# M452x.net
KiCad netlist of a schematic drawn in EAGLE
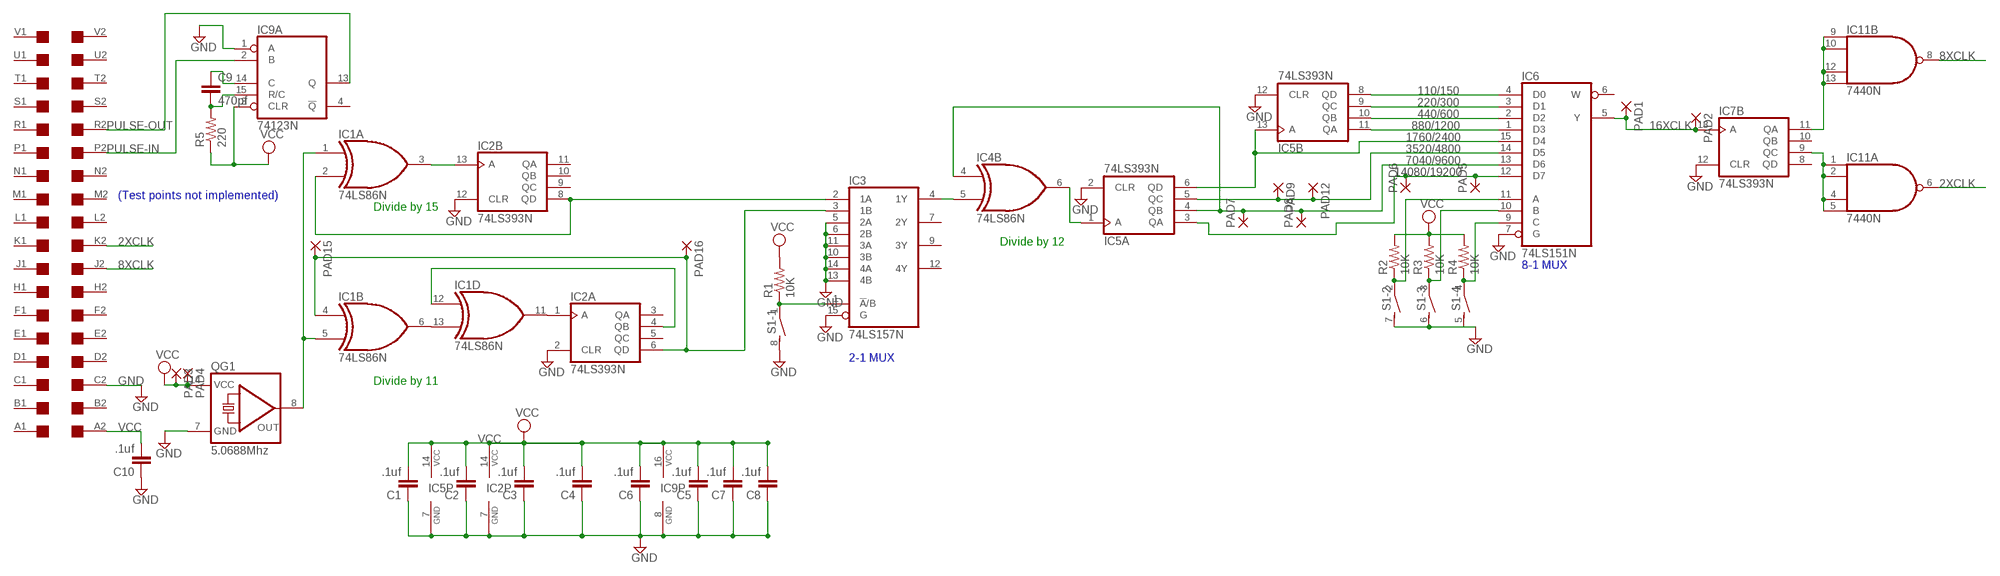
[diagram p0: schematic, sheet 1]

(export (version "E")
  (design (tool "Eeschema 10.0.6"))
  (components
    (comp (ref "C1")
      (value ".1uf")
      (footprint "eagle-import:C050-025X075")
      (libsource (lib "eagle-import") (part "C-EU050-025X075"))
    )
    (comp (ref "C2")
      (value ".1uf")
      (footprint "eagle-import:C050-025X075")
      (libsource (lib "eagle-import") (part "C-EU050-025X075"))
    )
    (comp (ref "C3")
      (value ".1uf")
      (footprint "eagle-import:C050-025X075")
      (libsource (lib "eagle-import") (part "C-EU050-025X075"))
    )
    (comp (ref "C4")
      (value ".1uf")
      (footprint "eagle-import:C050-025X075")
      (libsource (lib "eagle-import") (part "C-EU050-025X075"))
    )
    (comp (ref "C5")
      (value ".1uf")
      (footprint "eagle-import:C050-025X075")
      (libsource (lib "eagle-import") (part "C-EU050-025X075"))
    )
    (comp (ref "C6")
      (value ".1uf")
      (footprint "eagle-import:C050-025X075")
      (libsource (lib "eagle-import") (part "C-EU050-025X075"))
    )
    (comp (ref "C7")
      (value ".1uf")
      (footprint "eagle-import:C050-025X075")
      (libsource (lib "eagle-import") (part "C-EU050-025X075"))
    )
    (comp (ref "C8")
      (value ".1uf")
      (footprint "eagle-import:C050-025X075")
      (libsource (lib "eagle-import") (part "C-EU050-025X075"))
    )
    (comp (ref "C9")
      (value "470pf")
      (footprint "eagle-import:C050-025X075")
      (libsource (lib "eagle-import") (part "C-EU050-025X075"))
    )
    (comp (ref "C10")
      (value ".1uf")
      (footprint "eagle-import:C050-025X075")
      (libsource (lib "eagle-import") (part "C-EU050-025X075"))
    )
    (comp (ref "IC1")
      (value "74LS86N")
      (footprint "eagle-import:DIL14")
      (libsource (lib "eagle-import") (part "7486NLS"))
    )
    (comp (ref "IC2")
      (value "74LS393N")
      (footprint "eagle-import:DIL14")
      (libsource (lib "eagle-import") (part "74393NLS"))
    )
    (comp (ref "IC3")
      (value "74LS157N")
      (footprint "eagle-import:DIL16")
      (libsource (lib "eagle-import") (part "74157NLS"))
    )
    (comp (ref "IC4")
      (value "74LS86N")
      (footprint "eagle-import:DIL14")
      (libsource (lib "eagle-import") (part "7486NLS"))
    )
    (comp (ref "IC5")
      (value "74LS393N")
      (footprint "eagle-import:DIL14")
      (libsource (lib "eagle-import") (part "74393NLS"))
    )
    (comp (ref "IC6")
      (value "74LS151N")
      (footprint "eagle-import:DIL16")
      (libsource (lib "eagle-import") (part "74151N"))
    )
    (comp (ref "IC7")
      (value "74LS393N")
      (footprint "eagle-import:DIL14")
      (libsource (lib "eagle-import") (part "74393NLS"))
    )
    (comp (ref "IC9")
      (value "74123N")
      (footprint "eagle-import:DIL16")
      (libsource (lib "eagle-import") (part "74123N"))
    )
    (comp (ref "IC11")
      (value "7440N")
      (footprint "eagle-import:DIL14")
      (libsource (lib "eagle-import") (part "7420NS"))
    )
    (comp (ref "PAD1")
      (value "1,6/0,8")
      (footprint "eagle-import:1,6_0,8")
      (libsource (lib "eagle-import") (part "1,6/0,8"))
    )
    (comp (ref "PAD2")
      (value "1,6/0,8")
      (footprint "eagle-import:1,6_0,8")
      (libsource (lib "eagle-import") (part "1,6/0,8"))
    )
    (comp (ref "PAD3")
      (value "1,6/0,8")
      (footprint "eagle-import:1,6_0,8")
      (libsource (lib "eagle-import") (part "1,6/0,8"))
    )
    (comp (ref "PAD4")
      (value "1,6/0,8")
      (footprint "eagle-import:1,6_0,8")
      (libsource (lib "eagle-import") (part "1,6/0,8"))
    )
    (comp (ref "PAD5")
      (value "1,6/0,8")
      (footprint "eagle-import:1,6_0,8")
      (libsource (lib "eagle-import") (part "1,6/0,8"))
    )
    (comp (ref "PAD6")
      (value "1,6/0,8")
      (footprint "eagle-import:1,6_0,8")
      (libsource (lib "eagle-import") (part "1,6/0,8"))
    )
    (comp (ref "PAD7")
      (value "1,6/0,8")
      (footprint "eagle-import:1,6_0,8")
      (libsource (lib "eagle-import") (part "1,6/0,8"))
    )
    (comp (ref "PAD8")
      (value "1,6/0,8")
      (footprint "eagle-import:1,6_0,8")
      (libsource (lib "eagle-import") (part "1,6/0,8"))
    )
    (comp (ref "PAD9")
      (value "1,6/0,8")
      (footprint "eagle-import:1,6_0,8")
      (libsource (lib "eagle-import") (part "1,6/0,8"))
    )
    (comp (ref "PAD12")
      (value "1,6/0,8")
      (footprint "eagle-import:1,6_0,8")
      (libsource (lib "eagle-import") (part "1,6/0,8"))
    )
    (comp (ref "PAD15")
      (value "1,6/0,8")
      (footprint "eagle-import:1,6_0,8")
      (libsource (lib "eagle-import") (part "1,6/0,8"))
    )
    (comp (ref "PAD16")
      (value "1,6/0,8")
      (footprint "eagle-import:1,6_0,8")
      (libsource (lib "eagle-import") (part "1,6/0,8"))
    )
    (comp (ref "QG1")
      (value "5.0688Mhz")
      (footprint "eagle-import:DIL14S")
      (libsource (lib "eagle-import") (part "QG5860"))
    )
    (comp (ref "R1")
      (value "10K")
      (footprint "eagle-import:0204_7")
      (libsource (lib "eagle-import") (part "R-US_0204/7"))
    )
    (comp (ref "R2")
      (value "10K")
      (footprint "eagle-import:0204_7")
      (libsource (lib "eagle-import") (part "R-US_0204/7"))
    )
    (comp (ref "R3")
      (value "10K")
      (footprint "eagle-import:0204_7")
      (libsource (lib "eagle-import") (part "R-US_0204/7"))
    )
    (comp (ref "R4")
      (value "10K")
      (footprint "eagle-import:0204_7")
      (libsource (lib "eagle-import") (part "R-US_0204/7"))
    )
    (comp (ref "R5")
      (value "220")
      (footprint "eagle-import:0204_7")
      (libsource (lib "eagle-import") (part "R-US_0204/7"))
    )
    (comp (ref "S1")
      (value "DIP04S")
      (footprint "eagle-import:DIP04S")
      (libsource (lib "eagle-import") (part "DIP04S"))
    )
    (comp (ref "U$1")
      (value "DEC-FLIPCHIP")
      (footprint "eagle-import:DEC-FLIPCHIP")
      (libsource (lib "eagle-import") (part "DEC-FLIPCHIP"))
    )
  )
  (nets
    (net (code "1") (name "/2XCLK") (class "Default")
      (node (ref "IC11") (pin "6") (pinfunction "O_6") (pintype "output"))
      (node (ref "U$1") (pin "K2") (pinfunction "K2_K2") (pintype "passive"))
    )
    (net (code "2") (name "/8XCLK") (class "Default")
      (node (ref "IC11") (pin "8") (pinfunction "O_8") (pintype "output"))
      (node (ref "U$1") (pin "J2") (pinfunction "J2_J2") (pintype "passive"))
    )
    (net (code "3") (name "/16XCLK") (class "Default")
      (node (ref "IC6") (pin "5") (pinfunction "Y_5") (pintype "output"))
      (node (ref "IC7") (pin "13") (pinfunction "A_13") (pintype "input"))
      (node (ref "PAD1") (pin "1") (pinfunction "P_1") (pintype "passive"))
      (node (ref "PAD2") (pin "1") (pinfunction "P_1") (pintype "passive"))
    )
    (net (code "4") (name "/110{slash}150") (class "Default")
      (node (ref "IC5") (pin "8") (pinfunction "QD_8") (pintype "output"))
      (node (ref "IC6") (pin "4") (pinfunction "D0_4") (pintype "input"))
    )
    (net (code "5") (name "/220{slash}300") (class "Default")
      (node (ref "IC5") (pin "9") (pinfunction "QC_9") (pintype "output"))
      (node (ref "IC6") (pin "3") (pinfunction "D1_3") (pintype "input"))
    )
    (net (code "6") (name "/440{slash}600") (class "Default")
      (node (ref "IC5") (pin "10") (pinfunction "QB_10") (pintype "output"))
      (node (ref "IC6") (pin "2") (pinfunction "D2_2") (pintype "input"))
    )
    (net (code "7") (name "/880{slash}1200") (class "Default")
      (node (ref "IC5") (pin "11") (pinfunction "QA_11") (pintype "output"))
      (node (ref "IC6") (pin "1") (pinfunction "D3_1") (pintype "input"))
    )
    (net (code "8") (name "/1760{slash}2400") (class "Default")
      (node (ref "IC5") (pin "13") (pinfunction "A_13") (pintype "input"))
      (node (ref "IC5") (pin "6") (pinfunction "QD_6") (pintype "output"))
      (node (ref "IC6") (pin "15") (pinfunction "D4_15") (pintype "input"))
    )
    (net (code "9") (name "/3520{slash}4800") (class "Default")
      (node (ref "IC5") (pin "5") (pinfunction "QC_5") (pintype "output"))
      (node (ref "IC6") (pin "14") (pinfunction "D5_14") (pintype "input"))
      (node (ref "PAD12") (pin "1") (pinfunction "P_1") (pintype "passive"))
      (node (ref "PAD9") (pin "1") (pinfunction "P_1") (pintype "passive"))
    )
    (net (code "10") (name "/7040{slash}9600") (class "Default")
      (node (ref "IC4") (pin "4") (pinfunction "I0_4") (pintype "input"))
      (node (ref "IC5") (pin "4") (pinfunction "QB_4") (pintype "output"))
      (node (ref "IC6") (pin "13") (pinfunction "D6_13") (pintype "input"))
      (node (ref "PAD7") (pin "1") (pinfunction "P_1") (pintype "passive"))
      (node (ref "PAD8") (pin "1") (pinfunction "P_1") (pintype "passive"))
    )
    (net (code "11") (name "/14080{slash}19200") (class "Default")
      (node (ref "IC5") (pin "3") (pinfunction "QA_3") (pintype "output"))
      (node (ref "IC6") (pin "12") (pinfunction "D7_12") (pintype "input"))
      (node (ref "PAD5") (pin "1") (pinfunction "P_1") (pintype "passive"))
      (node (ref "PAD6") (pin "1") (pinfunction "P_1") (pintype "passive"))
    )
    (net (code "12") (name "/PULSE-IN") (class "Default")
      (node (ref "IC9") (pin "2") (pinfunction "B_2") (pintype "input"))
      (node (ref "U$1") (pin "P2") (pinfunction "P2_P2") (pintype "passive"))
    )
    (net (code "13") (name "/PULSE-OUT") (class "Default")
      (node (ref "IC9") (pin "13") (pinfunction "Q_13") (pintype "output"))
      (node (ref "U$1") (pin "R2") (pinfunction "R2_R2") (pintype "passive"))
    )
    (net (code "14") (name "GND") (class "Default")
      (node (ref "C1") (pin "1") (pinfunction "1_1") (pintype "passive"))
      (node (ref "C10") (pin "1") (pinfunction "1_1") (pintype "passive"))
      (node (ref "C2") (pin "1") (pinfunction "1_1") (pintype "passive"))
      (node (ref "C3") (pin "1") (pinfunction "1_1") (pintype "passive"))
      (node (ref "C4") (pin "1") (pinfunction "1_1") (pintype "passive"))
      (node (ref "C5") (pin "1") (pinfunction "1_1") (pintype "passive"))
      (node (ref "C6") (pin "1") (pinfunction "1_1") (pintype "passive"))
      (node (ref "C7") (pin "1") (pinfunction "1_1") (pintype "passive"))
      (node (ref "C8") (pin "1") (pinfunction "1_1") (pintype "passive"))
      (node (ref "IC2") (pin "12") (pinfunction "CLR_12") (pintype "input"))
      (node (ref "IC2") (pin "2") (pinfunction "CLR_2") (pintype "input"))
      (node (ref "IC2") (pin "7") (pinfunction "GND_7") (pintype "power_in"))
      (node (ref "IC3") (pin "10") (pinfunction "3B_10") (pintype "input"))
      (node (ref "IC3") (pin "11") (pinfunction "3A_11") (pintype "input"))
      (node (ref "IC3") (pin "13") (pinfunction "4B_13") (pintype "input"))
      (node (ref "IC3") (pin "14") (pinfunction "4A_14") (pintype "input"))
      (node (ref "IC3") (pin "15") (pinfunction "G_15") (pintype "input"))
      (node (ref "IC3") (pin "5") (pinfunction "2A_5") (pintype "input"))
      (node (ref "IC3") (pin "6") (pinfunction "2B_6") (pintype "input"))
      (node (ref "IC5") (pin "12") (pinfunction "CLR_12") (pintype "input"))
      (node (ref "IC5") (pin "2") (pinfunction "CLR_2") (pintype "input"))
      (node (ref "IC5") (pin "7") (pinfunction "GND_7") (pintype "power_in"))
      (node (ref "IC6") (pin "7") (pinfunction "G_7") (pintype "input"))
      (node (ref "IC7") (pin "12") (pinfunction "CLR_12") (pintype "input"))
      (node (ref "IC9") (pin "1") (pinfunction "A_1") (pintype "input"))
      (node (ref "IC9") (pin "8") (pinfunction "GND_8") (pintype "power_in"))
      (node (ref "QG1") (pin "7") (pinfunction "GND_7") (pintype "power_in"))
      (node (ref "S1") (pin "5") (pinfunction "2_5") (pintype "passive"))
      (node (ref "S1") (pin "6") (pinfunction "2_6") (pintype "passive"))
      (node (ref "S1") (pin "7") (pinfunction "2_7") (pintype "passive"))
      (node (ref "S1") (pin "8") (pinfunction "2_8") (pintype "passive"))
      (node (ref "U$1") (pin "C2") (pinfunction "C2_C2") (pintype "passive"))
    )
    (net (code "15") (name "Net-(IC1A-I0)") (class "Default")
      (node (ref "IC1") (pin "1") (pinfunction "I0_1") (pintype "input"))
      (node (ref "IC1") (pin "5") (pinfunction "I1_5") (pintype "input"))
      (node (ref "QG1") (pin "8") (pinfunction "OUT_8") (pintype "output"))
    )
    (net (code "16") (name "Net-(IC1A-I1)") (class "Default")
      (node (ref "IC1") (pin "2") (pinfunction "I1_2") (pintype "input"))
      (node (ref "IC2") (pin "8") (pinfunction "QD_8") (pintype "output"))
      (node (ref "IC3") (pin "2") (pinfunction "1A_2") (pintype "input"))
    )
    (net (code "17") (name "Net-(IC1A-O)") (class "Default")
      (node (ref "IC1") (pin "3") (pinfunction "O_3") (pintype "output"))
      (node (ref "IC2") (pin "13") (pinfunction "A_13") (pintype "input"))
    )
    (net (code "18") (name "Net-(IC1B-I0)") (class "Default")
      (node (ref "IC1") (pin "4") (pinfunction "I0_4") (pintype "input"))
      (node (ref "IC2") (pin "6") (pinfunction "QD_6") (pintype "output"))
      (node (ref "IC3") (pin "3") (pinfunction "1B_3") (pintype "input"))
      (node (ref "PAD15") (pin "1") (pinfunction "P_1") (pintype "passive"))
      (node (ref "PAD16") (pin "1") (pinfunction "P_1") (pintype "passive"))
    )
    (net (code "19") (name "Net-(IC1B-O)") (class "Default")
      (node (ref "IC1") (pin "13") (pinfunction "I1_13") (pintype "input"))
      (node (ref "IC1") (pin "6") (pinfunction "O_6") (pintype "output"))
    )
    (net (code "20") (name "Net-(IC1D-I0)") (class "Default")
      (node (ref "IC1") (pin "12") (pinfunction "I0_12") (pintype "input"))
      (node (ref "IC2") (pin "4") (pinfunction "QB_4") (pintype "output"))
    )
    (net (code "21") (name "Net-(IC1D-O)") (class "Default")
      (node (ref "IC1") (pin "11") (pinfunction "O_11") (pintype "output"))
      (node (ref "IC2") (pin "1") (pinfunction "A_1") (pintype "input"))
    )
    (net (code "22") (name "Net-(IC3A-1Y)") (class "Default")
      (node (ref "IC3") (pin "4") (pinfunction "1Y_4") (pintype "output"))
      (node (ref "IC4") (pin "5") (pinfunction "I1_5") (pintype "input"))
    )
    (net (code "23") (name "Net-(IC3A-~{A}{slash}B)") (class "Default")
      (node (ref "IC3") (pin "1") (pinfunction "~{A}/B_1") (pintype "input"))
      (node (ref "R1") (pin "1") (pinfunction "1_1") (pintype "passive"))
      (node (ref "S1") (pin "1") (pinfunction "1_1") (pintype "passive"))
    )
    (net (code "24") (name "Net-(IC4B-O)") (class "Default")
      (node (ref "IC4") (pin "6") (pinfunction "O_6") (pintype "output"))
      (node (ref "IC5") (pin "1") (pinfunction "A_1") (pintype "input"))
    )
    (net (code "25") (name "Net-(IC6A-A)") (class "Default")
      (node (ref "IC6") (pin "11") (pinfunction "A_11") (pintype "input"))
      (node (ref "R2") (pin "1") (pinfunction "1_1") (pintype "passive"))
      (node (ref "S1") (pin "2") (pinfunction "1_2") (pintype "passive"))
    )
    (net (code "26") (name "Net-(IC6A-B)") (class "Default")
      (node (ref "IC6") (pin "10") (pinfunction "B_10") (pintype "input"))
      (node (ref "R3") (pin "1") (pinfunction "1_1") (pintype "passive"))
      (node (ref "S1") (pin "3") (pinfunction "1_3") (pintype "passive"))
    )
    (net (code "27") (name "Net-(IC6A-C)") (class "Default")
      (node (ref "IC6") (pin "9") (pinfunction "C_9") (pintype "input"))
      (node (ref "R4") (pin "1") (pinfunction "1_1") (pintype "passive"))
      (node (ref "S1") (pin "4") (pinfunction "1_4") (pintype "passive"))
    )
    (net (code "28") (name "Net-(IC9A-C)") (class "Default")
      (node (ref "C9") (pin "1") (pinfunction "1_1") (pintype "passive"))
      (node (ref "IC9") (pin "14") (pinfunction "C_14") (pintype "input"))
    )
    (net (code "29") (name "Net-(IC9A-R{slash}C)") (class "Default")
      (node (ref "C9") (pin "2") (pinfunction "2_2") (pintype "passive"))
      (node (ref "IC9") (pin "15") (pinfunction "R/C_15") (pintype "input"))
      (node (ref "R5") (pin "2") (pinfunction "2_2") (pintype "passive"))
    )
    (net (code "30") (name "Net-(IC11A-I0)") (class "Default")
      (node (ref "IC11") (pin "1") (pinfunction "I0_1") (pintype "input"))
      (node (ref "IC11") (pin "2") (pinfunction "I1_2") (pintype "input"))
      (node (ref "IC11") (pin "4") (pinfunction "I2_4") (pintype "input"))
      (node (ref "IC11") (pin "5") (pinfunction "I3_5") (pintype "input"))
      (node (ref "IC7") (pin "9") (pinfunction "QC_9") (pintype "output"))
    )
    (net (code "31") (name "Net-(IC11B-I0)") (class "Default")
      (node (ref "IC11") (pin "10") (pinfunction "I1_10") (pintype "input"))
      (node (ref "IC11") (pin "12") (pinfunction "I2_12") (pintype "input"))
      (node (ref "IC11") (pin "13") (pinfunction "I3_13") (pintype "input"))
      (node (ref "IC11") (pin "9") (pinfunction "I0_9") (pintype "input"))
      (node (ref "IC7") (pin "11") (pinfunction "QA_11") (pintype "output"))
    )
    (net (code "32") (name "VCC") (class "Default")
      (node (ref "C1") (pin "2") (pinfunction "2_2") (pintype "passive"))
      (node (ref "C10") (pin "2") (pinfunction "2_2") (pintype "passive"))
      (node (ref "C2") (pin "2") (pinfunction "2_2") (pintype "passive"))
      (node (ref "C3") (pin "2") (pinfunction "2_2") (pintype "passive"))
      (node (ref "C4") (pin "2") (pinfunction "2_2") (pintype "passive"))
      (node (ref "C5") (pin "2") (pinfunction "2_2") (pintype "passive"))
      (node (ref "C6") (pin "2") (pinfunction "2_2") (pintype "passive"))
      (node (ref "C7") (pin "2") (pinfunction "2_2") (pintype "passive"))
      (node (ref "C8") (pin "2") (pinfunction "2_2") (pintype "passive"))
      (node (ref "IC2") (pin "14") (pinfunction "VCC_14") (pintype "power_in"))
      (node (ref "IC5") (pin "14") (pinfunction "VCC_14") (pintype "power_in"))
      (node (ref "IC9") (pin "16") (pinfunction "VCC_16") (pintype "power_in"))
      (node (ref "IC9") (pin "3") (pinfunction "CLR_3") (pintype "input"))
      (node (ref "PAD3") (pin "1") (pinfunction "P_1") (pintype "passive"))
      (node (ref "PAD4") (pin "1") (pinfunction "P_1") (pintype "passive"))
      (node (ref "QG1") (pin "14") (pinfunction "VCC_14") (pintype "power_in"))
      (node (ref "R1") (pin "2") (pinfunction "2_2") (pintype "passive"))
      (node (ref "R2") (pin "2") (pinfunction "2_2") (pintype "passive"))
      (node (ref "R3") (pin "2") (pinfunction "2_2") (pintype "passive"))
      (node (ref "R4") (pin "2") (pinfunction "2_2") (pintype "passive"))
      (node (ref "R5") (pin "1") (pinfunction "1_1") (pintype "passive"))
      (node (ref "U$1") (pin "A2") (pinfunction "A2_A2") (pintype "passive"))
    )
    (net (code "33") (name "unconnected-(IC2A-QA-Pad3)") (class "Default")
      (node (ref "IC2") (pin "3") (pinfunction "QA_3") (pintype "output"))
    )
    (net (code "34") (name "unconnected-(IC2A-QC-Pad5)") (class "Default")
      (node (ref "IC2") (pin "5") (pinfunction "QC_5") (pintype "output"))
    )
    (net (code "35") (name "unconnected-(IC2B-QA-Pad11)") (class "Default")
      (node (ref "IC2") (pin "11") (pinfunction "QA_11") (pintype "output"))
    )
    (net (code "36") (name "unconnected-(IC2B-QB-Pad10)") (class "Default")
      (node (ref "IC2") (pin "10") (pinfunction "QB_10") (pintype "output"))
    )
    (net (code "37") (name "unconnected-(IC2B-QC-Pad9)") (class "Default")
      (node (ref "IC2") (pin "9") (pinfunction "QC_9") (pintype "output"))
    )
    (net (code "38") (name "unconnected-(IC3A-2Y-Pad7)") (class "Default")
      (node (ref "IC3") (pin "7") (pinfunction "2Y_7") (pintype "output"))
    )
    (net (code "39") (name "unconnected-(IC3A-3Y-Pad9)") (class "Default")
      (node (ref "IC3") (pin "9") (pinfunction "3Y_9") (pintype "output"))
    )
    (net (code "40") (name "unconnected-(IC3A-4Y-Pad12)") (class "Default")
      (node (ref "IC3") (pin "12") (pinfunction "4Y_12") (pintype "output"))
    )
    (net (code "41") (name "unconnected-(IC6A-W-Pad6)") (class "Default")
      (node (ref "IC6") (pin "6") (pinfunction "W_6") (pintype "output"))
    )
    (net (code "42") (name "unconnected-(IC7B-QB-Pad10)") (class "Default")
      (node (ref "IC7") (pin "10") (pinfunction "QB_10") (pintype "output"))
    )
    (net (code "43") (name "unconnected-(IC7B-QD-Pad8)") (class "Default")
      (node (ref "IC7") (pin "8") (pinfunction "QD_8") (pintype "output"))
    )
    (net (code "44") (name "unconnected-(IC9A-~{Q}-Pad4)") (class "Default")
      (node (ref "IC9") (pin "4") (pinfunction "~{Q}_4") (pintype "output"))
    )
    (net (code "45") (name "unconnected-(U$1-PadA1)") (class "Default")
      (node (ref "U$1") (pin "A1") (pinfunction "A1_A1") (pintype "passive"))
    )
    (net (code "46") (name "unconnected-(U$1-PadB1)") (class "Default")
      (node (ref "U$1") (pin "B1") (pinfunction "B1_B1") (pintype "passive"))
    )
    (net (code "47") (name "unconnected-(U$1-PadB2)") (class "Default")
      (node (ref "U$1") (pin "B2") (pinfunction "B2_B2") (pintype "passive"))
    )
    (net (code "48") (name "unconnected-(U$1-PadC1)") (class "Default")
      (node (ref "U$1") (pin "C1") (pinfunction "C1_C1") (pintype "passive"))
    )
    (net (code "49") (name "unconnected-(U$1-PadD1)") (class "Default")
      (node (ref "U$1") (pin "D1") (pinfunction "D1_D1") (pintype "passive"))
    )
    (net (code "50") (name "unconnected-(U$1-PadD2)") (class "Default")
      (node (ref "U$1") (pin "D2") (pinfunction "D2_D2") (pintype "passive"))
    )
    (net (code "51") (name "unconnected-(U$1-PadE1)") (class "Default")
      (node (ref "U$1") (pin "E1") (pinfunction "E1_E1") (pintype "passive"))
    )
    (net (code "52") (name "unconnected-(U$1-PadE2)") (class "Default")
      (node (ref "U$1") (pin "E2") (pinfunction "E2_E2") (pintype "passive"))
    )
    (net (code "53") (name "unconnected-(U$1-PadF1)") (class "Default")
      (node (ref "U$1") (pin "F1") (pinfunction "F1_F1") (pintype "passive"))
    )
    (net (code "54") (name "unconnected-(U$1-PadF2)") (class "Default")
      (node (ref "U$1") (pin "F2") (pinfunction "F2_F2") (pintype "passive"))
    )
    (net (code "55") (name "unconnected-(U$1-PadH1)") (class "Default")
      (node (ref "U$1") (pin "H1") (pinfunction "H1_H1") (pintype "passive"))
    )
    (net (code "56") (name "unconnected-(U$1-PadH2)") (class "Default")
      (node (ref "U$1") (pin "H2") (pinfunction "H2_H2") (pintype "passive"))
    )
    (net (code "57") (name "unconnected-(U$1-PadJ1)") (class "Default")
      (node (ref "U$1") (pin "J1") (pinfunction "J1_J1") (pintype "passive"))
    )
    (net (code "58") (name "unconnected-(U$1-PadK1)") (class "Default")
      (node (ref "U$1") (pin "K1") (pinfunction "K1_K1") (pintype "passive"))
    )
    (net (code "59") (name "unconnected-(U$1-PadL1)") (class "Default")
      (node (ref "U$1") (pin "L1") (pinfunction "L1_L1") (pintype "passive"))
    )
    (net (code "60") (name "unconnected-(U$1-PadL2)") (class "Default")
      (node (ref "U$1") (pin "L2") (pinfunction "L2_L2") (pintype "passive"))
    )
    (net (code "61") (name "unconnected-(U$1-PadM1)") (class "Default")
      (node (ref "U$1") (pin "M1") (pinfunction "M1_M1") (pintype "passive"))
    )
    (net (code "62") (name "unconnected-(U$1-PadM2)") (class "Default")
      (node (ref "U$1") (pin "M2") (pinfunction "M2_M2") (pintype "passive"))
    )
    (net (code "63") (name "unconnected-(U$1-PadN1)") (class "Default")
      (node (ref "U$1") (pin "N1") (pinfunction "N1_N1") (pintype "passive"))
    )
    (net (code "64") (name "unconnected-(U$1-PadN2)") (class "Default")
      (node (ref "U$1") (pin "N2") (pinfunction "N2_N2") (pintype "passive"))
    )
    (net (code "65") (name "unconnected-(U$1-PadP1)") (class "Default")
      (node (ref "U$1") (pin "P1") (pinfunction "P1_P1") (pintype "passive"))
    )
    (net (code "66") (name "unconnected-(U$1-PadR1)") (class "Default")
      (node (ref "U$1") (pin "R1") (pinfunction "R1_R1") (pintype "passive"))
    )
    (net (code "67") (name "unconnected-(U$1-PadS1)") (class "Default")
      (node (ref "U$1") (pin "S1") (pinfunction "S1_S1") (pintype "passive"))
    )
    (net (code "68") (name "unconnected-(U$1-PadS2)") (class "Default")
      (node (ref "U$1") (pin "S2") (pinfunction "S2_S2") (pintype "passive"))
    )
    (net (code "69") (name "unconnected-(U$1-PadT1)") (class "Default")
      (node (ref "U$1") (pin "T1") (pinfunction "T1_T1") (pintype "passive"))
    )
    (net (code "70") (name "unconnected-(U$1-PadT2)") (class "Default")
      (node (ref "U$1") (pin "T2") (pinfunction "T2_T2") (pintype "passive"))
    )
    (net (code "71") (name "unconnected-(U$1-PadU1)") (class "Default")
      (node (ref "U$1") (pin "U1") (pinfunction "U1_U1") (pintype "passive"))
    )
    (net (code "72") (name "unconnected-(U$1-PadU2)") (class "Default")
      (node (ref "U$1") (pin "U2") (pinfunction "U2_U2") (pintype "passive"))
    )
    (net (code "73") (name "unconnected-(U$1-PadV1)") (class "Default")
      (node (ref "U$1") (pin "V1") (pinfunction "V1_V1") (pintype "passive"))
    )
    (net (code "74") (name "unconnected-(U$1-PadV2)") (class "Default")
      (node (ref "U$1") (pin "V2") (pinfunction "V2_V2") (pintype "passive"))
    )
  )
)
